# usb-pickit2-adapter.net
KiCad netlist of a schematic drawn in EAGLE
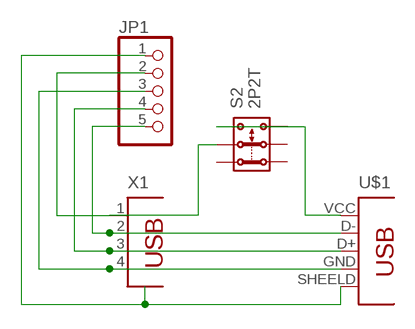
[diagram p0: schematic, sheet 1]

(export (version "E")
  (design (tool "Eeschema 10.0.6"))
  (components
    (comp (ref "JP1")
      (value "PINHD-1X5")
      (footprint "eagle-import:1X05")
      (libsource (lib "eagle-import") (part "PINHD-1X5"))
    )
    (comp (ref "S2")
      (value "2P2T")
      (footprint "eagle-import:2P2T")
      (libsource (lib "eagle-import") (part "2P2T"))
    )
    (comp (ref "U$1")
      (value "TYPE-A+SHILED")
      (footprint "eagle-import:TYPE-A")
      (libsource (lib "eagle-import") (part "TYPE-A+SHILED"))
    )
    (comp (ref "X1")
      (value "PN87520")
      (footprint "eagle-import:PN87520")
      (libsource (lib "eagle-import") (part "PN87520"))
    )
  )
  (nets
    (net (code "1") (name "Net-(JP1-Pad2)") (class "Default")
      (node (ref "JP1") (pin "2") (pinfunction "2_2") (pintype "passive"))
      (node (ref "S2") (pin "2.1") (pinfunction "2.1_2.1") (pintype "passive"))
      (node (ref "X1") (pin "1") (pinfunction "1_1") (pintype "passive"))
    )
    (net (code "2") (name "Net-(U$1-1)") (class "Default")
      (node (ref "S2") (pin "3.1") (pinfunction "3.1_3.1") (pintype "passive"))
      (node (ref "U$1") (pin "VCC") (pinfunction "1_VCC") (pintype "power_in"))
    )
    (net (code "3") (name "Net-(U$1-2)") (class "Default")
      (node (ref "JP1") (pin "5") (pinfunction "5_5") (pintype "passive"))
      (node (ref "U$1") (pin "D-") (pinfunction "2_D-") (pintype "passive"))
      (node (ref "X1") (pin "2") (pinfunction "2_2") (pintype "passive"))
    )
    (net (code "4") (name "Net-(U$1-3)") (class "Default")
      (node (ref "JP1") (pin "4") (pinfunction "4_4") (pintype "passive"))
      (node (ref "U$1") (pin "D+") (pinfunction "3_D+") (pintype "passive"))
      (node (ref "X1") (pin "3") (pinfunction "3_3") (pintype "passive"))
    )
    (net (code "5") (name "Net-(U$1-4)") (class "Default")
      (node (ref "JP1") (pin "3") (pinfunction "3_3") (pintype "passive"))
      (node (ref "U$1") (pin "GND") (pinfunction "4_GND") (pintype "power_in"))
      (node (ref "X1") (pin "4") (pinfunction "4_4") (pintype "passive"))
    )
    (net (code "6") (name "Net-(U$1-5)") (class "Default")
      (node (ref "JP1") (pin "1") (pinfunction "1_1") (pintype "passive"))
      (node (ref "U$1") (pin "SHEELD") (pinfunction "5_SHEELD") (pintype "passive"))
    )
    (net (code "7") (name "unconnected-(S2-Pad1.1)") (class "Default")
      (node (ref "S2") (pin "1.1") (pinfunction "1.1_1.1") (pintype "passive"))
    )
    (net (code "8") (name "unconnected-(S2-Pad1.2)") (class "Default")
      (node (ref "S2") (pin "1.2") (pinfunction "1.2_1.2") (pintype "passive"))
    )
    (net (code "9") (name "unconnected-(S2-Pad2.2)") (class "Default")
      (node (ref "S2") (pin "2.2") (pinfunction "2.2_2.2") (pintype "passive"))
    )
    (net (code "10") (name "unconnected-(S2-Pad3.2)") (class "Default")
      (node (ref "S2") (pin "3.2") (pinfunction "3.2_3.2") (pintype "passive"))
    )
  )
)
